# Sensor.net
KiCad netlist of a schematic drawn in Altium Designer
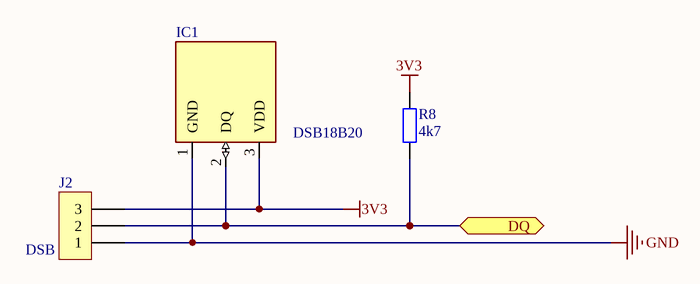
[diagram p0: Sensor.SchDoc]

(export (version "E")
  (design (tool "Eeschema 10.0.6"))
  (components
    (comp (ref "IC1")
      (value "DSB18B20")
      (footprint "TO-92")
      (description "https://linhkien.cxt.vn/3083-ds18b20-temperature-sensors-55-to-125-c-to-92-3.html")
      (libsource (lib "Main") (part "DSB18B20"))
    )
    (comp (ref "J2")
      (value "DSB")
      (footprint "KF3-5.08")
      (fields
        (field (name "MANUFACTURER") "Würth Elektronik eiSos GmbH")
        (field (name "PARTNO") "691103110003")
        (field (name "CREATED BY") "Karrer Zheng")
      )
      (libsource (lib "Main") (part "KF3"))
    )
    (comp (ref "R8")
      (value "4k7")
      (footprint "RES-SMD-0805")
      (description "Resistor SMD")
      (fields
        (field (name "MANUFACTURER") "Generic Components")
        (field (name "PUBLISHER") "Altium Hobart Technology Centre")
      )
      (libsource (lib "Main") (part "Resistor - SMD"))
    )
  )
  (nets
    (net (code "1") (name "/DQ") (class "Default")
      (node (ref "IC1") (pin "2") (pinfunction "DQ_2") (pintype "bidirectional"))
      (node (ref "J2") (pin "2") (pinfunction "2_2") (pintype "passive"))
      (node (ref "R8") (pin "1") (pinfunction "1_1") (pintype "passive"))
    )
    (net (code "2") (name "3V3") (class "Default")
      (node (ref "IC1") (pin "3") (pinfunction "VDD_3") (pintype "power_in"))
      (node (ref "J2") (pin "3") (pinfunction "3_3") (pintype "passive"))
      (node (ref "R8") (pin "2") (pinfunction "2_2") (pintype "passive"))
    )
    (net (code "3") (name "GND") (class "Default")
      (node (ref "IC1") (pin "1") (pinfunction "GND_1") (pintype "power_in"))
      (node (ref "J2") (pin "1") (pinfunction "1_1") (pintype "passive"))
    )
  )
)
